# 001_top.net
KiCad netlist of a schematic drawn in Altium Designer
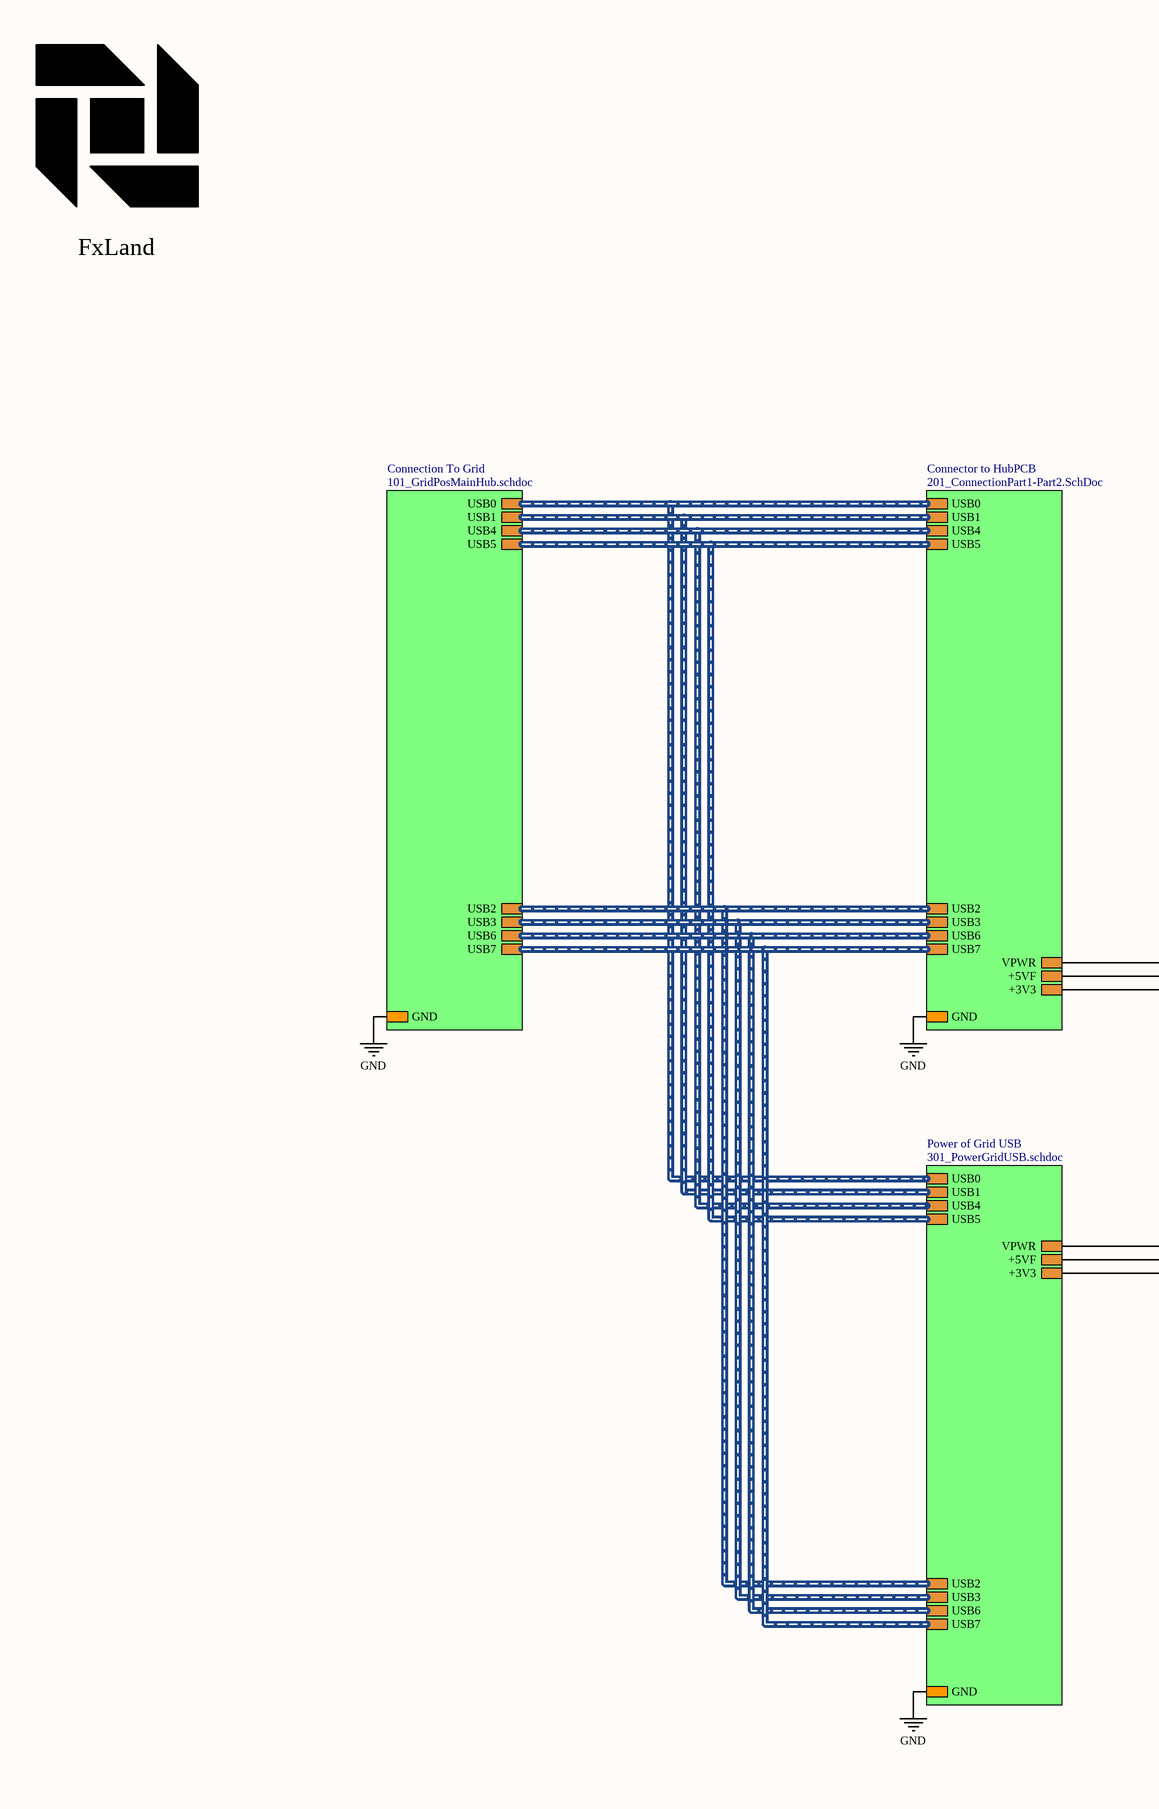
[diagram p0: 001_top.SchDoc, left]
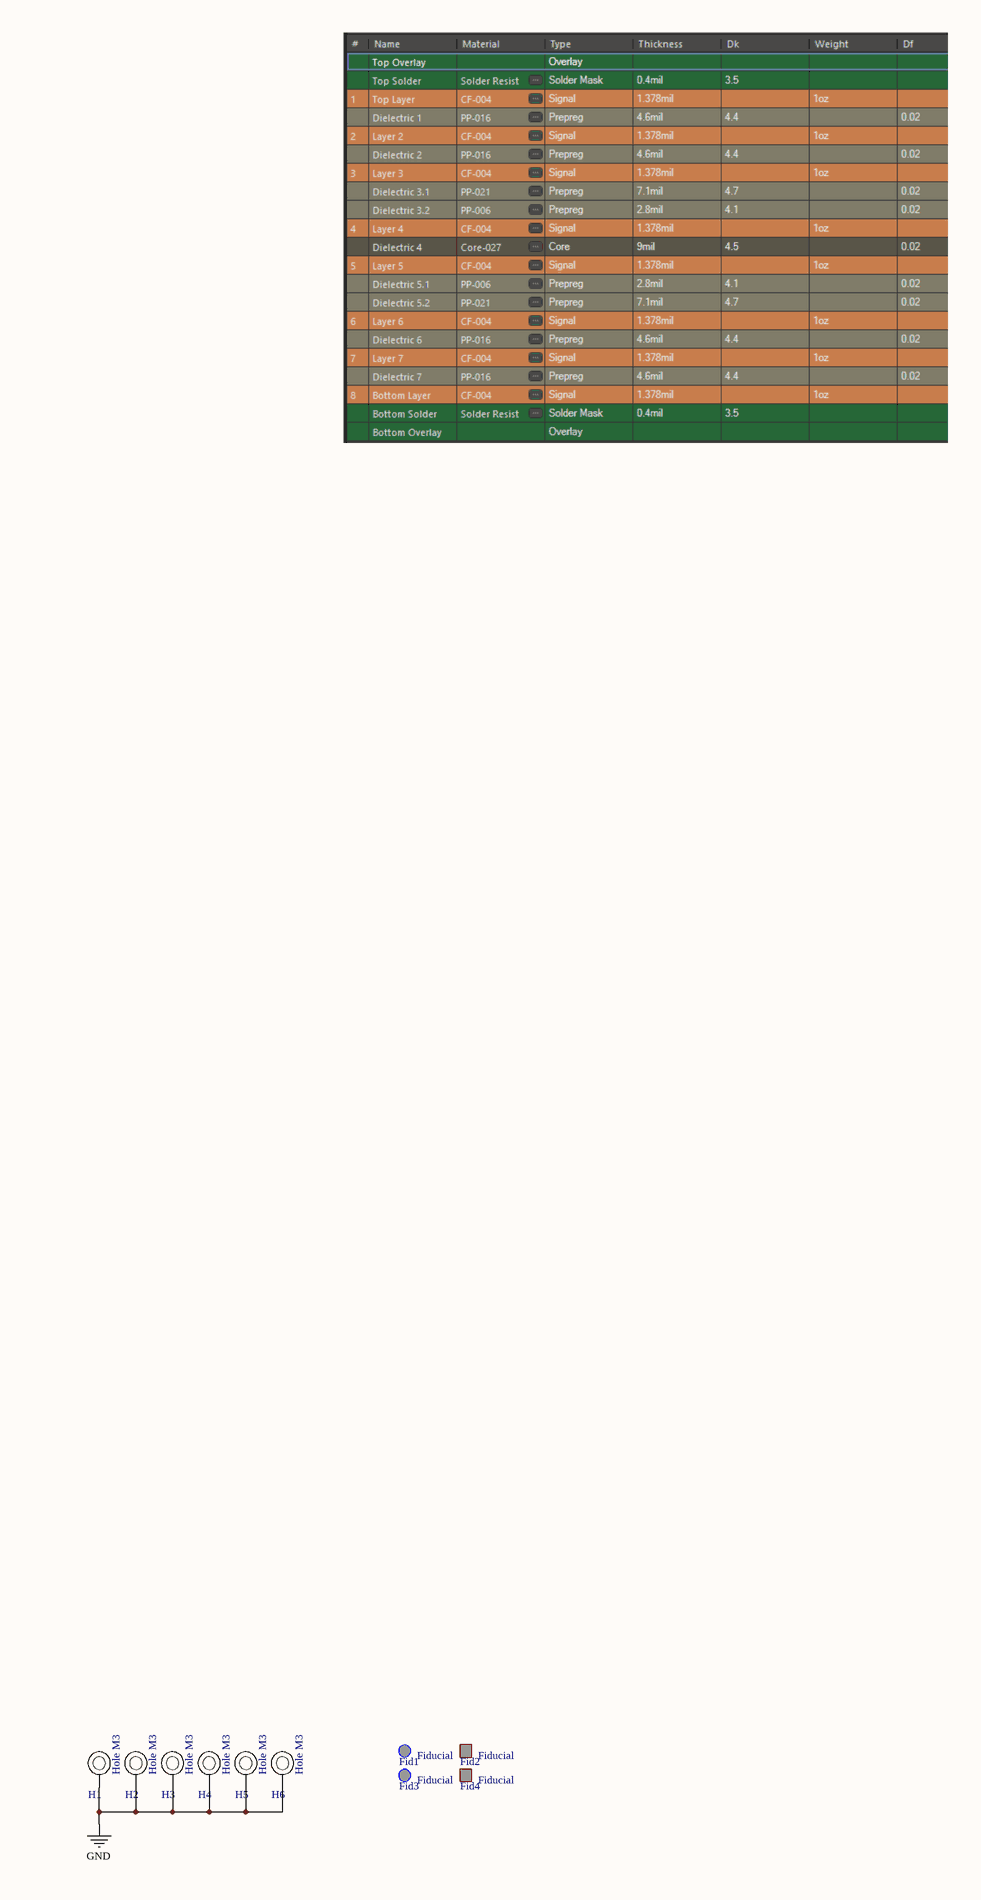
[diagram p1: 001_top.SchDoc, right]

(export (version "E")
  (design (tool "Eeschema 10.0.6"))
  (components
    (comp (ref "Fid1")
      (value "Fiducial")
      (footprint "FidR_1.0mm")
      (description "Fiducial Round 1mm")
      (fields (field (name "REFVAL") "Fiducial") (field (name "PART NUMBER") "ME0011"))
      (libsource (lib "GTS_Database") (part "FidR_1.0mm"))
    )
    (comp (ref "Fid2")
      (value "Fiducial")
      (footprint "FidS_1.0mm")
      (description "Fiducial Sqaure 1mm")
      (fields (field (name "REFVAL") "Fiducial") (field (name "PART NUMBER") "ME0012"))
      (libsource (lib "GTS_Database") (part "FidS_1.0mm"))
    )
    (comp (ref "Fid3")
      (value "Fiducial")
      (footprint "FidR_1.0mm")
      (description "Fiducial Round 1mm")
      (fields (field (name "REFVAL") "Fiducial") (field (name "PART NUMBER") "ME0011"))
      (libsource (lib "GTS_Database") (part "FidR_1.0mm"))
    )
    (comp (ref "Fid4")
      (value "Fiducial")
      (footprint "FidS_1.0mm")
      (description "Fiducial Sqaure 1mm")
      (fields (field (name "REFVAL") "Fiducial") (field (name "PART NUMBER") "ME0012"))
      (libsource (lib "GTS_Database") (part "FidS_1.0mm"))
    )
    (comp (ref "H1")
      (value "Hole M3")
      (footprint "HOLE_M3")
      (description "Mounting Hole M3")
      (fields (field (name "REFVAL") "Hole M3") (field (name "PART NUMBER") "ME0001"))
      (libsource (lib "GTS_Database") (part "HOLE"))
    )
    (comp (ref "H2")
      (value "Hole M3")
      (footprint "HOLE_M3")
      (description "Mounting Hole M3")
      (fields (field (name "REFVAL") "Hole M3") (field (name "PART NUMBER") "ME0001"))
      (libsource (lib "GTS_Database") (part "HOLE"))
    )
    (comp (ref "H3")
      (value "Hole M3")
      (footprint "HOLE_M3")
      (description "Mounting Hole M3")
      (fields (field (name "REFVAL") "Hole M3") (field (name "PART NUMBER") "ME0001"))
      (libsource (lib "GTS_Database") (part "HOLE"))
    )
    (comp (ref "H4")
      (value "Hole M3")
      (footprint "HOLE_M3")
      (description "Mounting Hole M3")
      (fields (field (name "REFVAL") "Hole M3") (field (name "PART NUMBER") "ME0001"))
      (libsource (lib "GTS_Database") (part "HOLE"))
    )
    (comp (ref "H5")
      (value "Hole M3")
      (footprint "HOLE_M3")
      (description "Mounting Hole M3")
      (fields (field (name "REFVAL") "Hole M3") (field (name "PART NUMBER") "ME0001"))
      (libsource (lib "GTS_Database") (part "HOLE"))
    )
    (comp (ref "H6")
      (value "Hole M3")
      (footprint "HOLE_M3")
      (description "Mounting Hole M3")
      (fields (field (name "REFVAL") "Hole M3") (field (name "PART NUMBER") "ME0001"))
      (libsource (lib "GTS_Database") (part "HOLE"))
    )
    (comp (ref "Logo FxLand1")
      (value "FxLand")
      (footprint "Logo_FxLand_3")
      (description "Logo FxLand 3")
      (fields (field (name "PART NUMBER") "ME0008"))
      (libsource (lib "GTS_Database") (part "Logo_FxLand_2"))
    )
  )
  (nets
    (net (code "20") (name "GND") (class "Default")
      (node (ref "H1") (pin "1") (pinfunction "1_1") (pintype "passive"))
      (node (ref "H2") (pin "1") (pinfunction "1_1") (pintype "passive"))
      (node (ref "H3") (pin "1") (pinfunction "1_1") (pintype "passive"))
      (node (ref "H4") (pin "1") (pinfunction "1_1") (pintype "passive"))
      (node (ref "H5") (pin "1") (pinfunction "1_1") (pintype "passive"))
      (node (ref "H6") (pin "1") (pinfunction "1_1") (pintype "passive"))
    )
  )
)
